# EMP4.net
KiCad netlist of a schematic drawn in EAGLE
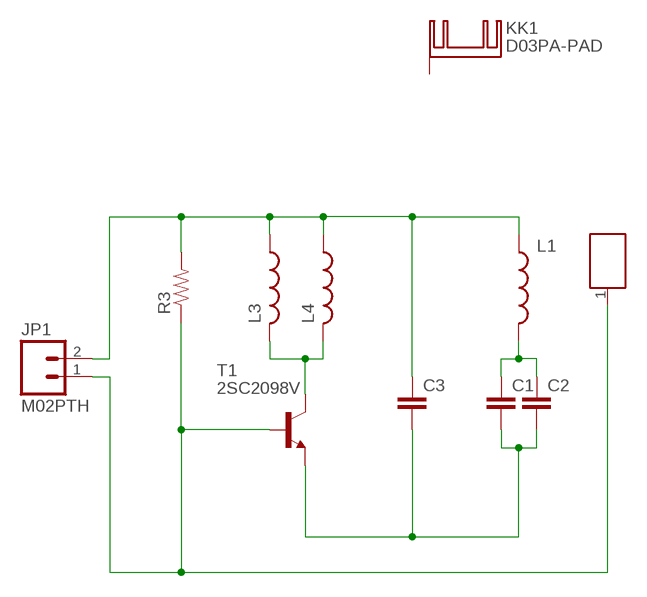
[diagram p0: schematic, sheet 1]

(export (version "E")
  (design (tool "Eeschema 10.0.6"))
  (components
    (comp (ref "C1")
      (value "CAPEZ")
      (footprint "eagle-import:CAP-PTH-SMALLEZ")
      (libsource (lib "eagle-import") (part "CAPEZ"))
    )
    (comp (ref "C2")
      (value "CAPEZ")
      (footprint "eagle-import:CAP-PTH-SMALLEZ")
      (libsource (lib "eagle-import") (part "CAPEZ"))
    )
    (comp (ref "C3")
      (value "CAPEZ")
      (footprint "eagle-import:CAP-PTH-SMALLEZ")
      (libsource (lib "eagle-import") (part "CAPEZ"))
    )
    (comp (ref "JP1")
      (value "M02PTH")
      (footprint "eagle-import:1X02")
      (libsource (lib "eagle-import") (part "M02PTH"))
    )
    (comp (ref "KK1")
      (value "D03PA-PAD")
      (footprint "eagle-import:D03PA-PAD")
      (libsource (lib "eagle-import") (part "D03PA-PAD"))
    )
    (comp (ref "L1")
      (value "INDUCTORCR54-KIT")
      (footprint "eagle-import:CR54-KIT")
      (libsource (lib "eagle-import") (part "INDUCTORCR54-KIT"))
    )
    (comp (ref "L3")
      (value "L-USTFI0307")
      (footprint "eagle-import:TFI0307")
      (libsource (lib "eagle-import") (part "L-USTFI0307"))
    )
    (comp (ref "L4")
      (value "L-USTFI0307")
      (footprint "eagle-import:TFI0307")
      (libsource (lib "eagle-import") (part "L-USTFI0307"))
    )
    (comp (ref "R3")
      (value "RESISTOREZ")
      (footprint "eagle-import:AXIAL-0.3EZ")
      (libsource (lib "eagle-import") (part "RESISTOREZ"))
    )
    (comp (ref "T1")
      (value "2SC2098V")
      (footprint "eagle-import:TO220AV")
      (libsource (lib "eagle-import") (part "2SC2098V"))
    )
    (comp (ref "U$1")
      (value "L2_JOB37")
      (footprint "eagle-import:L2_JOB37")
      (libsource (lib "eagle-import") (part "L2_JOB37"))
    )
  )
  (nets
    (net (code "1") (name "Net-(L1-1)") (class "Default")
      (node (ref "C3") (pin "1") (pinfunction "1_1") (pintype "passive"))
      (node (ref "JP1") (pin "2") (pinfunction "2_2") (pintype "passive"))
      (node (ref "L1") (pin "P$1") (pinfunction "1_P$1") (pintype "passive"))
      (node (ref "L3") (pin "1") (pinfunction "1_1") (pintype "passive"))
      (node (ref "L4") (pin "1") (pinfunction "1_1") (pintype "passive"))
      (node (ref "R3") (pin "P$2") (pinfunction "2_P$2") (pintype "passive"))
    )
    (net (code "2") (name "Net-(L1-2)") (class "Default")
      (node (ref "C1") (pin "1") (pinfunction "1_1") (pintype "passive"))
      (node (ref "C2") (pin "1") (pinfunction "1_1") (pintype "passive"))
      (node (ref "L1") (pin "P$2") (pinfunction "2_P$2") (pintype "passive"))
    )
    (net (code "3") (name "Net-(R3-1)") (class "Default")
      (node (ref "JP1") (pin "1") (pinfunction "1_1") (pintype "passive"))
      (node (ref "R3") (pin "P$1") (pinfunction "1_P$1") (pintype "passive"))
      (node (ref "T1") (pin "1") (pinfunction "B_1") (pintype "passive"))
      (node (ref "U$1") (pin "1") (pinfunction "1_1") (pintype "bidirectional"))
    )
    (net (code "4") (name "Net-(T1-C)") (class "Default")
      (node (ref "L3") (pin "2") (pinfunction "2_2") (pintype "passive"))
      (node (ref "L4") (pin "2") (pinfunction "2_2") (pintype "passive"))
      (node (ref "T1") (pin "2") (pinfunction "C_2") (pintype "passive"))
    )
    (net (code "5") (name "Net-(T1-E)") (class "Default")
      (node (ref "C1") (pin "2") (pinfunction "2_2") (pintype "passive"))
      (node (ref "C2") (pin "2") (pinfunction "2_2") (pintype "passive"))
      (node (ref "C3") (pin "2") (pinfunction "2_2") (pintype "passive"))
      (node (ref "T1") (pin "3") (pinfunction "E_3") (pintype "passive"))
    )
    (net (code "6") (name "unconnected-(KK1-K-PadB)") (class "Default")
      (node (ref "KK1") (pin "B") (pinfunction "K_B") (pintype "passive"))
    )
  )
)
